# ClockCtrl.net
KiCad netlist of a schematic drawn in EAGLE
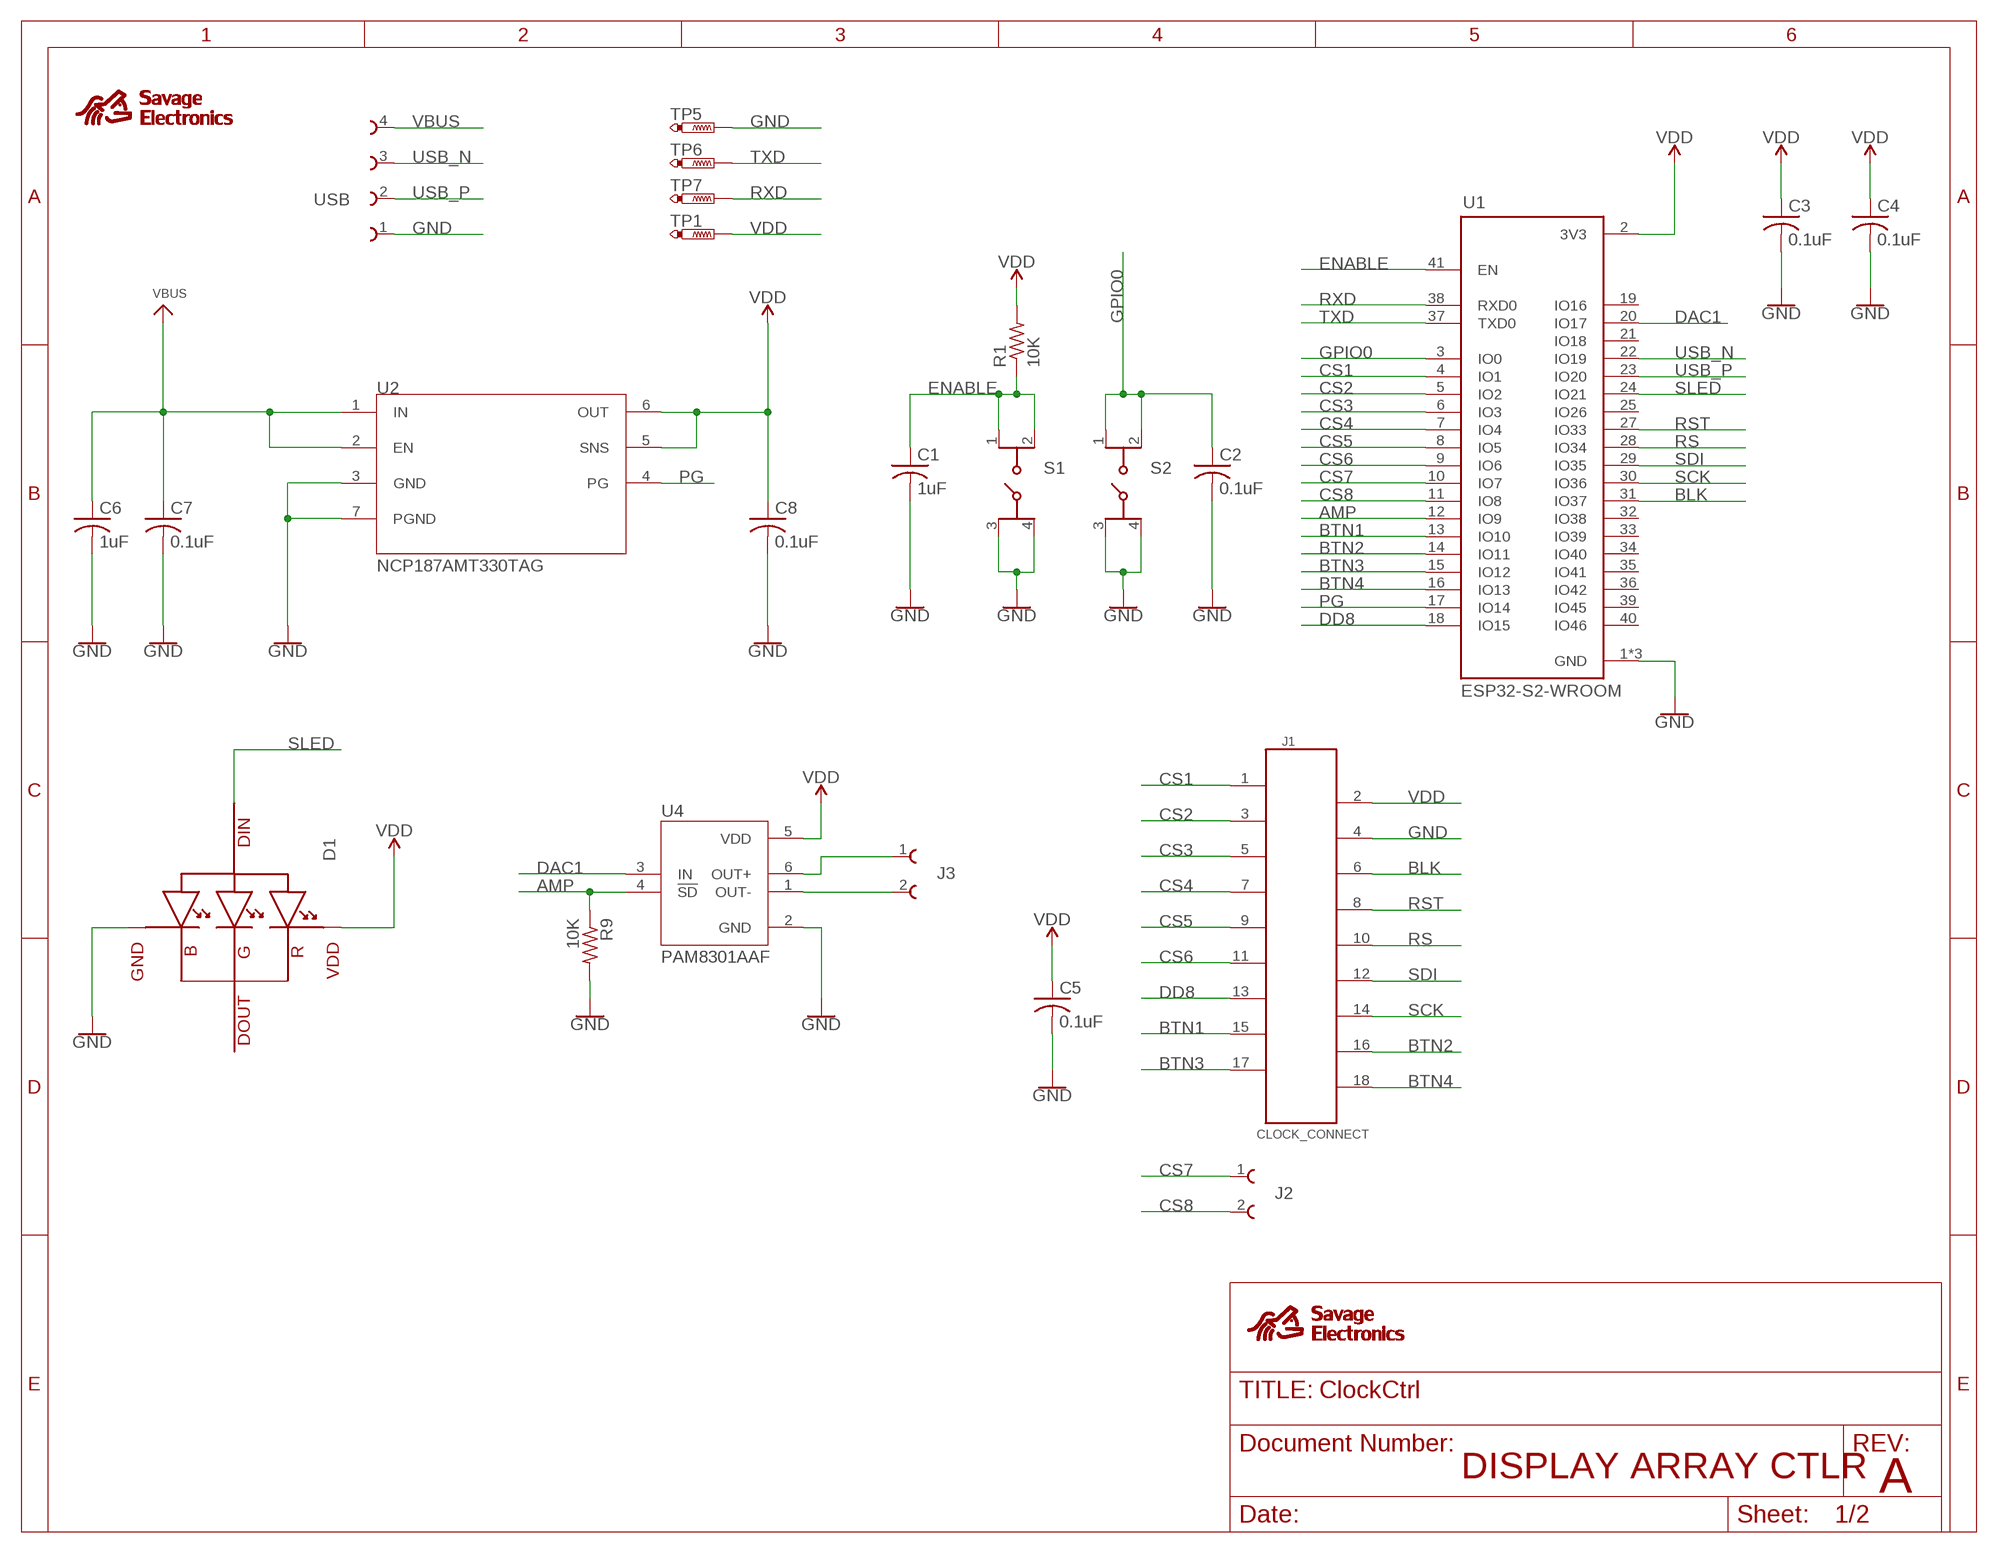
[diagram p0: schematic, sheet 1]
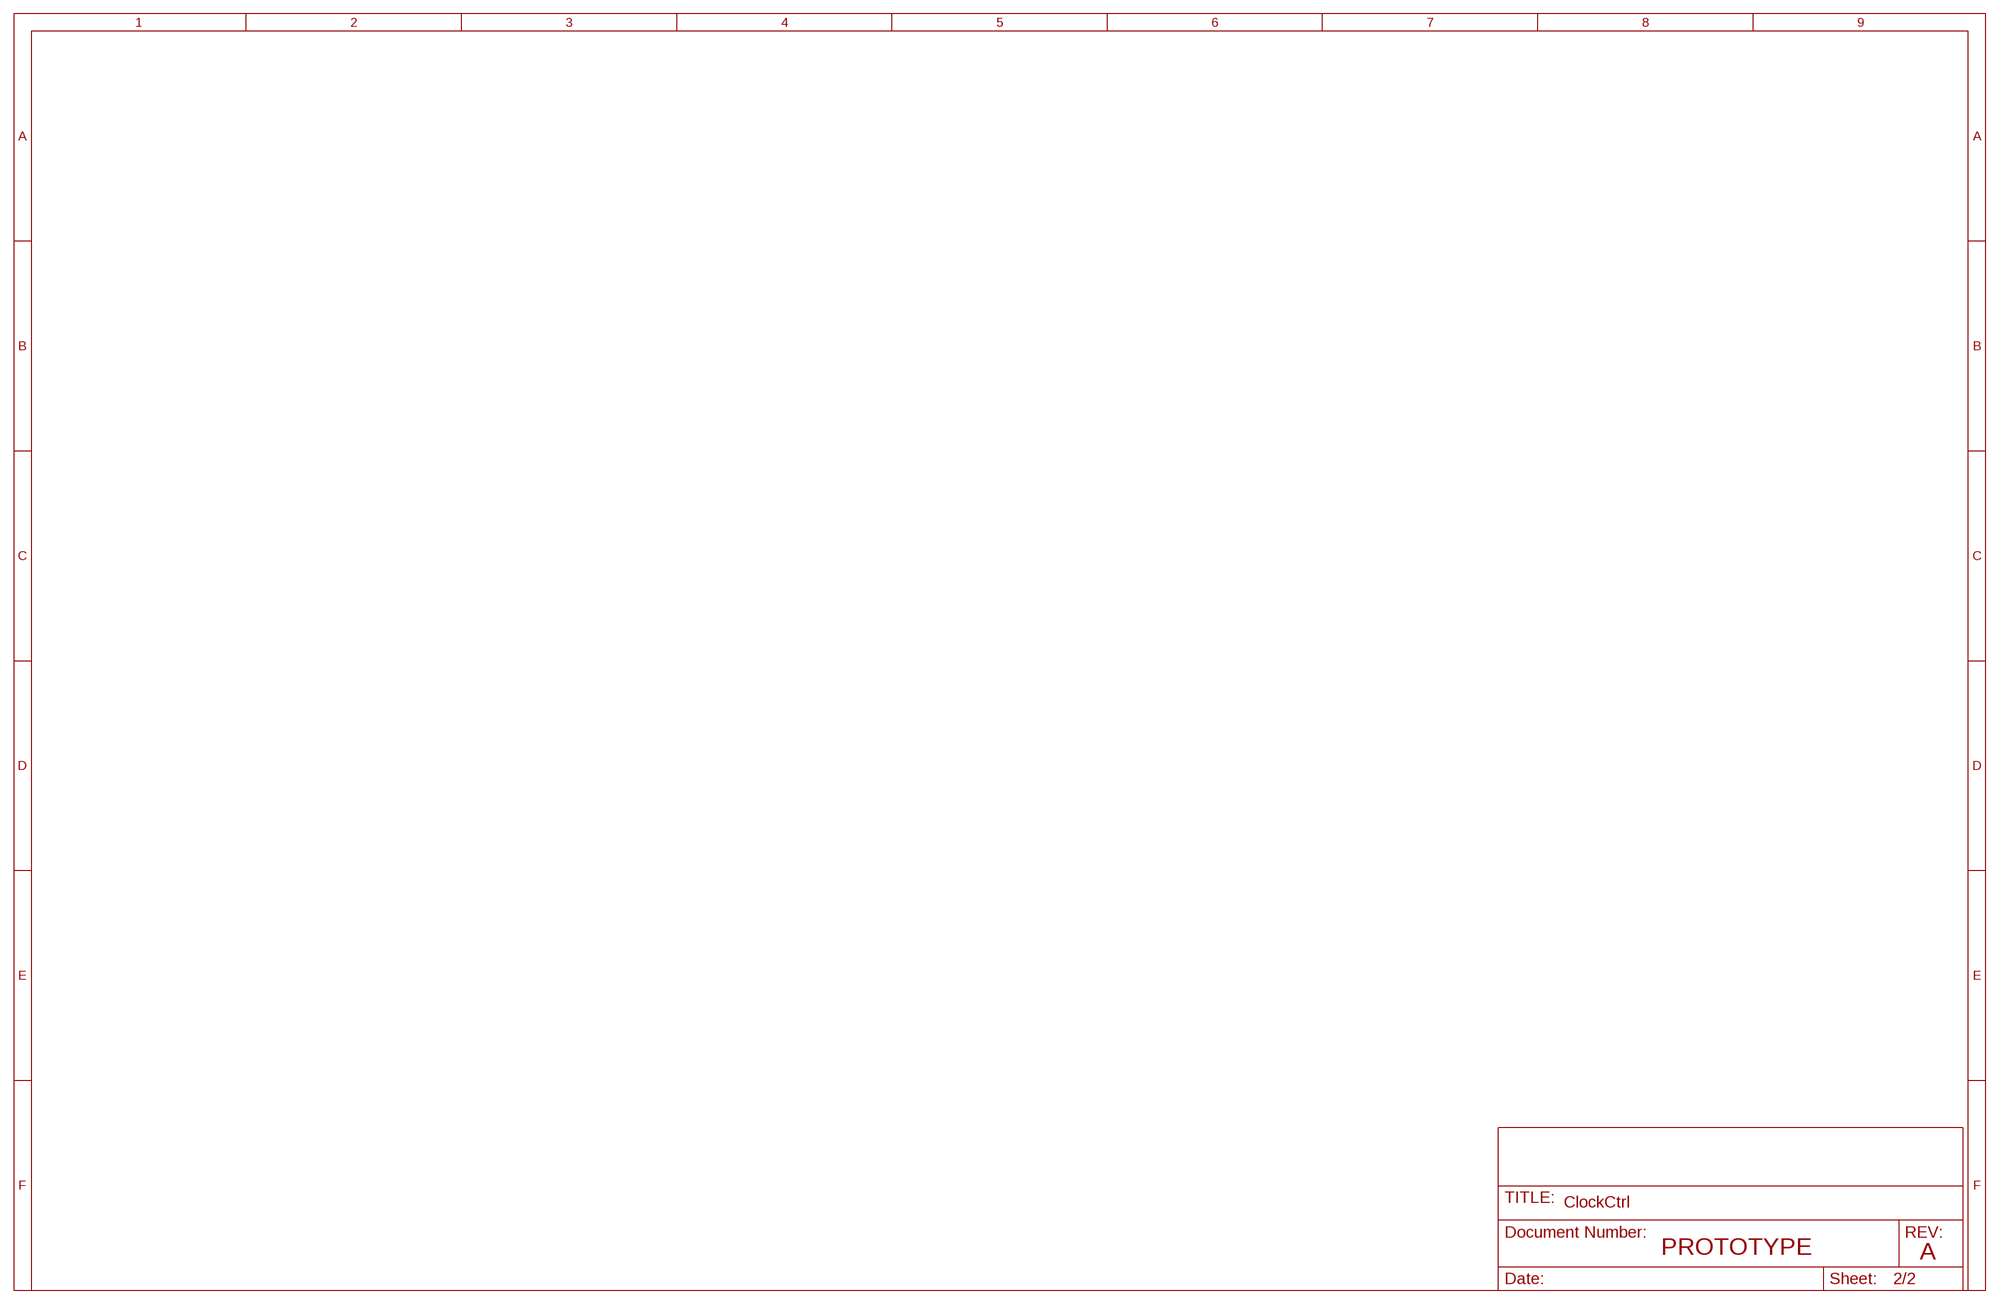
[diagram p1: schematic, sheet 2]

(export (version "E")
  (design (tool "Eeschema 10.0.6"))
  (components
    (comp (ref "C1")
      (value "1uF")
      (footprint "eagle-import:C0805")
      (libsource (lib "eagle-import") (part "C-USC0805"))
    )
    (comp (ref "C2")
      (value "0.1uF")
      (footprint "eagle-import:C0603")
      (libsource (lib "eagle-import") (part "C-USC0603"))
    )
    (comp (ref "C3")
      (value "0.1uF")
      (footprint "eagle-import:C0603")
      (libsource (lib "eagle-import") (part "C-USC0603"))
    )
    (comp (ref "C4")
      (value "0.1uF")
      (footprint "eagle-import:C0603")
      (libsource (lib "eagle-import") (part "C-USC0603"))
    )
    (comp (ref "C5")
      (value "0.1uF")
      (footprint "eagle-import:C0603")
      (libsource (lib "eagle-import") (part "C-USC0603"))
    )
    (comp (ref "C6")
      (value "1uF")
      (footprint "eagle-import:C0603")
      (libsource (lib "eagle-import") (part "C-USC0603"))
    )
    (comp (ref "C7")
      (value "0.1uF")
      (footprint "eagle-import:C0603")
      (libsource (lib "eagle-import") (part "C-USC0603"))
    )
    (comp (ref "C8")
      (value "0.1uF")
      (footprint "eagle-import:C0603")
      (libsource (lib "eagle-import") (part "C-USC0603"))
    )
    (comp (ref "D1")
      (value "SK6812")
      (footprint "eagle-import:20X20")
      (libsource (lib "eagle-import") (part "SK6812"))
    )
    (comp (ref "J1")
      (value "CLOCK_CONNECT")
      (footprint "eagle-import:CLOCKC_FOOTPRINT")
      (libsource (lib "eagle-import") (part "CLOCK_CONNECT"))
    )
    (comp (ref "J2")
      (value "62000211121")
      (footprint "eagle-import:62000211121")
      (libsource (lib "eagle-import") (part "62000211121"))
    )
    (comp (ref "J3")
      (value "62000211121")
      (footprint "eagle-import:62000211121")
      (libsource (lib "eagle-import") (part "62000211121"))
    )
    (comp (ref "R1")
      (value "10K")
      (footprint "eagle-import:R0603")
      (libsource (lib "eagle-import") (part "R-US_R0603"))
    )
    (comp (ref "R9")
      (value "10K")
      (footprint "eagle-import:R0603")
      (libsource (lib "eagle-import") (part "R-US_R0603"))
    )
    (comp (ref "S1")
      (value "434123025826")
      (footprint "eagle-import:434123025826")
      (libsource (lib "eagle-import") (part "434123025826"))
    )
    (comp (ref "S2")
      (value "434123025826")
      (footprint "eagle-import:434123025826")
      (libsource (lib "eagle-import") (part "434123025826"))
    )
    (comp (ref "TP1")
      (value "PTR1TP12R")
      (footprint "eagle-import:TP12R")
      (libsource (lib "eagle-import") (part "PTR1TP12R"))
    )
    (comp (ref "TP5")
      (value "PTR1TP12R")
      (footprint "eagle-import:TP12R")
      (libsource (lib "eagle-import") (part "PTR1TP12R"))
    )
    (comp (ref "TP6")
      (value "PTR1TP12R")
      (footprint "eagle-import:TP12R")
      (libsource (lib "eagle-import") (part "PTR1TP12R"))
    )
    (comp (ref "TP7")
      (value "PTR1TP12R")
      (footprint "eagle-import:TP12R")
      (libsource (lib "eagle-import") (part "PTR1TP12R"))
    )
    (comp (ref "U$1")
      (value "SE_SMALL_FSILK")
      (footprint "eagle-import:SE_SMALL_FACESILK")
      (libsource (lib "eagle-import") (part "SE_SMALL_FSILK"))
    )
    (comp (ref "U$3")
      (value "SE_SMALL_SILK")
      (footprint "eagle-import:SE_SMALL_SILK")
      (libsource (lib "eagle-import") (part "SE_SMALL_SILK"))
    )
    (comp (ref "U1")
      (value "ESP32-S2-WROOM")
      (footprint "eagle-import:XCVR_ESP32-S2-WROOM")
      (fields (field (name "MF") "Espressif Systems"))
      (libsource (lib "eagle-import") (part "ESP32-S2-WROOM"))
    )
    (comp (ref "U2")
      (value "NCP187AMT330TAG")
      (footprint "eagle-import:SON65P250X250X80-7N")
      (libsource (lib "eagle-import") (part "NCP187AMT330TAG"))
    )
    (comp (ref "U4")
      (value "PAM8301AAF")
      (footprint "eagle-import:SOT95P280X145-6N")
      (fields (field (name "MF") "Diodes Inc."))
      (libsource (lib "eagle-import") (part "PAM8301AAF"))
    )
    (comp (ref "USB")
      (value "62000411121")
      (footprint "eagle-import:62000411121")
      (libsource (lib "eagle-import") (part "62000411121"))
    )
  )
  (nets
    (net (code "1") (name "AMP") (class "Default")
      (node (ref "R9") (pin "1") (pinfunction "1_1") (pintype "passive"))
      (node (ref "U1") (pin "12") (pinfunction "IO9_12") (pintype "bidirectional"))
      (node (ref "U4") (pin "4") (pinfunction "~{SD}_4") (pintype "bidirectional"))
    )
    (net (code "2") (name "BLK") (class "Default")
      (node (ref "J1") (pin "6") (pinfunction "6_6") (pintype "passive"))
      (node (ref "U1") (pin "31") (pinfunction "IO37_31") (pintype "bidirectional"))
    )
    (net (code "3") (name "BTN1") (class "Default")
      (node (ref "J1") (pin "15") (pinfunction "15_15") (pintype "passive"))
      (node (ref "U1") (pin "13") (pinfunction "IO10_13") (pintype "bidirectional"))
    )
    (net (code "4") (name "BTN2") (class "Default")
      (node (ref "J1") (pin "16") (pinfunction "16_16") (pintype "passive"))
      (node (ref "U1") (pin "14") (pinfunction "IO11_14") (pintype "bidirectional"))
    )
    (net (code "5") (name "BTN3") (class "Default")
      (node (ref "J1") (pin "17") (pinfunction "17_17") (pintype "passive"))
      (node (ref "U1") (pin "15") (pinfunction "IO12_15") (pintype "bidirectional"))
    )
    (net (code "6") (name "BTN4") (class "Default")
      (node (ref "J1") (pin "18") (pinfunction "18_18") (pintype "passive"))
      (node (ref "U1") (pin "16") (pinfunction "IO13_16") (pintype "bidirectional"))
    )
    (net (code "7") (name "CS1") (class "Default")
      (node (ref "J1") (pin "1") (pinfunction "1_1") (pintype "passive"))
      (node (ref "U1") (pin "4") (pinfunction "IO1_4") (pintype "bidirectional"))
    )
    (net (code "8") (name "CS2") (class "Default")
      (node (ref "J1") (pin "3") (pinfunction "3_3") (pintype "passive"))
      (node (ref "U1") (pin "5") (pinfunction "IO2_5") (pintype "bidirectional"))
    )
    (net (code "9") (name "CS3") (class "Default")
      (node (ref "J1") (pin "5") (pinfunction "5_5") (pintype "passive"))
      (node (ref "U1") (pin "6") (pinfunction "IO3_6") (pintype "bidirectional"))
    )
    (net (code "10") (name "CS4") (class "Default")
      (node (ref "J1") (pin "7") (pinfunction "7_7") (pintype "passive"))
      (node (ref "U1") (pin "7") (pinfunction "IO4_7") (pintype "bidirectional"))
    )
    (net (code "11") (name "CS5") (class "Default")
      (node (ref "J1") (pin "9") (pinfunction "9_9") (pintype "passive"))
      (node (ref "U1") (pin "8") (pinfunction "IO5_8") (pintype "bidirectional"))
    )
    (net (code "12") (name "CS6") (class "Default")
      (node (ref "J1") (pin "11") (pinfunction "11_11") (pintype "passive"))
      (node (ref "U1") (pin "9") (pinfunction "IO6_9") (pintype "bidirectional"))
    )
    (net (code "13") (name "CS7") (class "Default")
      (node (ref "J2") (pin "1") (pinfunction "1_1") (pintype "passive"))
      (node (ref "U1") (pin "10") (pinfunction "IO7_10") (pintype "bidirectional"))
    )
    (net (code "14") (name "CS8") (class "Default")
      (node (ref "J2") (pin "2") (pinfunction "2_2") (pintype "passive"))
      (node (ref "U1") (pin "11") (pinfunction "IO8_11") (pintype "bidirectional"))
    )
    (net (code "15") (name "DAC1") (class "Default")
      (node (ref "U1") (pin "20") (pinfunction "IO17_20") (pintype "bidirectional"))
      (node (ref "U4") (pin "3") (pinfunction "IN_3") (pintype "input"))
    )
    (net (code "16") (name "DD8") (class "Default")
      (node (ref "J1") (pin "13") (pinfunction "13_13") (pintype "passive"))
      (node (ref "U1") (pin "18") (pinfunction "IO15_18") (pintype "bidirectional"))
    )
    (net (code "17") (name "ENABLE") (class "Default")
      (node (ref "C1") (pin "1") (pinfunction "1_1") (pintype "passive"))
      (node (ref "R1") (pin "1") (pinfunction "1_1") (pintype "passive"))
      (node (ref "S1") (pin "1") (pinfunction "1_1") (pintype "passive"))
      (node (ref "S1") (pin "2") (pinfunction "2_2") (pintype "passive"))
      (node (ref "U1") (pin "41") (pinfunction "EN_41") (pintype "input"))
    )
    (net (code "18") (name "GND") (class "Default")
      (node (ref "C1") (pin "2") (pinfunction "2_2") (pintype "passive"))
      (node (ref "C2") (pin "2") (pinfunction "2_2") (pintype "passive"))
      (node (ref "C3") (pin "2") (pinfunction "2_2") (pintype "passive"))
      (node (ref "C4") (pin "2") (pinfunction "2_2") (pintype "passive"))
      (node (ref "C5") (pin "2") (pinfunction "2_2") (pintype "passive"))
      (node (ref "C6") (pin "2") (pinfunction "2_2") (pintype "passive"))
      (node (ref "C7") (pin "2") (pinfunction "2_2") (pintype "passive"))
      (node (ref "C8") (pin "2") (pinfunction "2_2") (pintype "passive"))
      (node (ref "D1") (pin "3") (pinfunction "GND_3") (pintype "bidirectional"))
      (node (ref "J1") (pin "4") (pinfunction "4_4") (pintype "passive"))
      (node (ref "R9") (pin "2") (pinfunction "2_2") (pintype "passive"))
      (node (ref "S1") (pin "3") (pinfunction "3_3") (pintype "passive"))
      (node (ref "S1") (pin "4") (pinfunction "4_4") (pintype "passive"))
      (node (ref "S2") (pin "3") (pinfunction "3_3") (pintype "passive"))
      (node (ref "S2") (pin "4") (pinfunction "4_4") (pintype "passive"))
      (node (ref "TP5") (pin "TP") (pinfunction "TP_TP") (pintype "input"))
      (node (ref "U1") (pin "1") (pinfunction "GND_1") (pintype "power_in"))
      (node (ref "U1") (pin "26") (pinfunction "GND_26") (pintype "power_in"))
      (node (ref "U1") (pin "42") (pinfunction "GND_42") (pintype "power_in"))
      (node (ref "U2") (pin "3") (pinfunction "GND_3") (pintype "bidirectional"))
      (node (ref "U2") (pin "7") (pinfunction "PGND_7") (pintype "bidirectional"))
      (node (ref "U4") (pin "2") (pinfunction "GND_2") (pintype "power_in"))
      (node (ref "USB") (pin "1") (pinfunction "1_1") (pintype "passive"))
    )
    (net (code "19") (name "GPIO0") (class "Default")
      (node (ref "C2") (pin "1") (pinfunction "1_1") (pintype "passive"))
      (node (ref "S2") (pin "1") (pinfunction "1_1") (pintype "passive"))
      (node (ref "S2") (pin "2") (pinfunction "2_2") (pintype "passive"))
      (node (ref "U1") (pin "3") (pinfunction "IO0_3") (pintype "bidirectional"))
    )
    (net (code "20") (name "Net-(U4-OUT+)") (class "Default")
      (node (ref "J3") (pin "1") (pinfunction "1_1") (pintype "passive"))
      (node (ref "U4") (pin "6") (pinfunction "OUT+_6") (pintype "output"))
    )
    (net (code "21") (name "Net-(U4-OUT-)") (class "Default")
      (node (ref "J3") (pin "2") (pinfunction "2_2") (pintype "passive"))
      (node (ref "U4") (pin "1") (pinfunction "OUT-_1") (pintype "output"))
    )
    (net (code "22") (name "PG") (class "Default")
      (node (ref "U1") (pin "17") (pinfunction "IO14_17") (pintype "bidirectional"))
      (node (ref "U2") (pin "4") (pinfunction "PG_4") (pintype "bidirectional"))
    )
    (net (code "23") (name "RS") (class "Default")
      (node (ref "J1") (pin "10") (pinfunction "10_10") (pintype "passive"))
      (node (ref "U1") (pin "28") (pinfunction "IO34_28") (pintype "bidirectional"))
    )
    (net (code "24") (name "RST") (class "Default")
      (node (ref "J1") (pin "8") (pinfunction "8_8") (pintype "passive"))
      (node (ref "U1") (pin "27") (pinfunction "IO33_27") (pintype "bidirectional"))
    )
    (net (code "25") (name "RXD") (class "Default")
      (node (ref "TP7") (pin "TP") (pinfunction "TP_TP") (pintype "input"))
      (node (ref "U1") (pin "38") (pinfunction "RXD0_38") (pintype "bidirectional"))
    )
    (net (code "26") (name "SCK") (class "Default")
      (node (ref "J1") (pin "14") (pinfunction "14_14") (pintype "passive"))
      (node (ref "U1") (pin "30") (pinfunction "IO36_30") (pintype "bidirectional"))
    )
    (net (code "27") (name "SDI") (class "Default")
      (node (ref "J1") (pin "12") (pinfunction "12_12") (pintype "passive"))
      (node (ref "U1") (pin "29") (pinfunction "IO35_29") (pintype "bidirectional"))
    )
    (net (code "28") (name "SLED") (class "Default")
      (node (ref "D1") (pin "4") (pinfunction "DIN_4") (pintype "bidirectional"))
      (node (ref "U1") (pin "24") (pinfunction "IO21_24") (pintype "bidirectional"))
    )
    (net (code "29") (name "TXD") (class "Default")
      (node (ref "TP6") (pin "TP") (pinfunction "TP_TP") (pintype "input"))
      (node (ref "U1") (pin "37") (pinfunction "TXD0_37") (pintype "bidirectional"))
    )
    (net (code "30") (name "USB_N") (class "Default")
      (node (ref "U1") (pin "22") (pinfunction "IO19_22") (pintype "bidirectional"))
      (node (ref "USB") (pin "3") (pinfunction "3_3") (pintype "passive"))
    )
    (net (code "31") (name "USB_P") (class "Default")
      (node (ref "U1") (pin "23") (pinfunction "IO20_23") (pintype "bidirectional"))
      (node (ref "USB") (pin "2") (pinfunction "2_2") (pintype "passive"))
    )
    (net (code "32") (name "VBUS") (class "Default")
      (node (ref "C6") (pin "1") (pinfunction "1_1") (pintype "passive"))
      (node (ref "C7") (pin "1") (pinfunction "1_1") (pintype "passive"))
      (node (ref "U2") (pin "1") (pinfunction "IN_1") (pintype "bidirectional"))
      (node (ref "U2") (pin "2") (pinfunction "EN_2") (pintype "bidirectional"))
      (node (ref "USB") (pin "4") (pinfunction "4_4") (pintype "passive"))
    )
    (net (code "33") (name "VDD") (class "Default")
      (node (ref "C3") (pin "1") (pinfunction "1_1") (pintype "passive"))
      (node (ref "C4") (pin "1") (pinfunction "1_1") (pintype "passive"))
      (node (ref "C5") (pin "1") (pinfunction "1_1") (pintype "passive"))
      (node (ref "C8") (pin "1") (pinfunction "1_1") (pintype "passive"))
      (node (ref "D1") (pin "1") (pinfunction "VDD_1") (pintype "bidirectional"))
      (node (ref "J1") (pin "2") (pinfunction "2_2") (pintype "passive"))
      (node (ref "R1") (pin "2") (pinfunction "2_2") (pintype "passive"))
      (node (ref "TP1") (pin "TP") (pinfunction "TP_TP") (pintype "input"))
      (node (ref "U1") (pin "2") (pinfunction "3V3_2") (pintype "power_in"))
      (node (ref "U2") (pin "5") (pinfunction "SNS_5") (pintype "bidirectional"))
      (node (ref "U2") (pin "6") (pinfunction "OUT_6") (pintype "bidirectional"))
      (node (ref "U4") (pin "5") (pinfunction "VDD_5") (pintype "power_in"))
    )
    (net (code "34") (name "unconnected-(D1-DOUT-Pad2)") (class "Default")
      (node (ref "D1") (pin "2") (pinfunction "DOUT_2") (pintype "bidirectional"))
    )
    (net (code "35") (name "unconnected-(U1-IO16-Pad19)") (class "Default")
      (node (ref "U1") (pin "19") (pinfunction "IO16_19") (pintype "bidirectional"))
    )
    (net (code "36") (name "unconnected-(U1-IO18-Pad21)") (class "Default")
      (node (ref "U1") (pin "21") (pinfunction "IO18_21") (pintype "bidirectional"))
    )
    (net (code "37") (name "unconnected-(U1-IO26-Pad25)") (class "Default")
      (node (ref "U1") (pin "25") (pinfunction "IO26_25") (pintype "bidirectional"))
    )
    (net (code "38") (name "unconnected-(U1-IO38-Pad32)") (class "Default")
      (node (ref "U1") (pin "32") (pinfunction "IO38_32") (pintype "bidirectional"))
    )
    (net (code "39") (name "unconnected-(U1-IO39-Pad33)") (class "Default")
      (node (ref "U1") (pin "33") (pinfunction "IO39_33") (pintype "bidirectional"))
    )
    (net (code "40") (name "unconnected-(U1-IO40-Pad34)") (class "Default")
      (node (ref "U1") (pin "34") (pinfunction "IO40_34") (pintype "bidirectional"))
    )
    (net (code "41") (name "unconnected-(U1-IO41-Pad35)") (class "Default")
      (node (ref "U1") (pin "35") (pinfunction "IO41_35") (pintype "bidirectional"))
    )
    (net (code "42") (name "unconnected-(U1-IO42-Pad36)") (class "Default")
      (node (ref "U1") (pin "36") (pinfunction "IO42_36") (pintype "bidirectional"))
    )
    (net (code "43") (name "unconnected-(U1-IO45-Pad39)") (class "Default")
      (node (ref "U1") (pin "39") (pinfunction "IO45_39") (pintype "bidirectional"))
    )
    (net (code "44") (name "unconnected-(U1-IO46-Pad40)") (class "Default")
      (node (ref "U1") (pin "40") (pinfunction "IO46_40") (pintype "bidirectional"))
    )
  )
)
